# Fritzen_Zero_P_r00.net
KiCad netlist of a schematic drawn in EAGLE
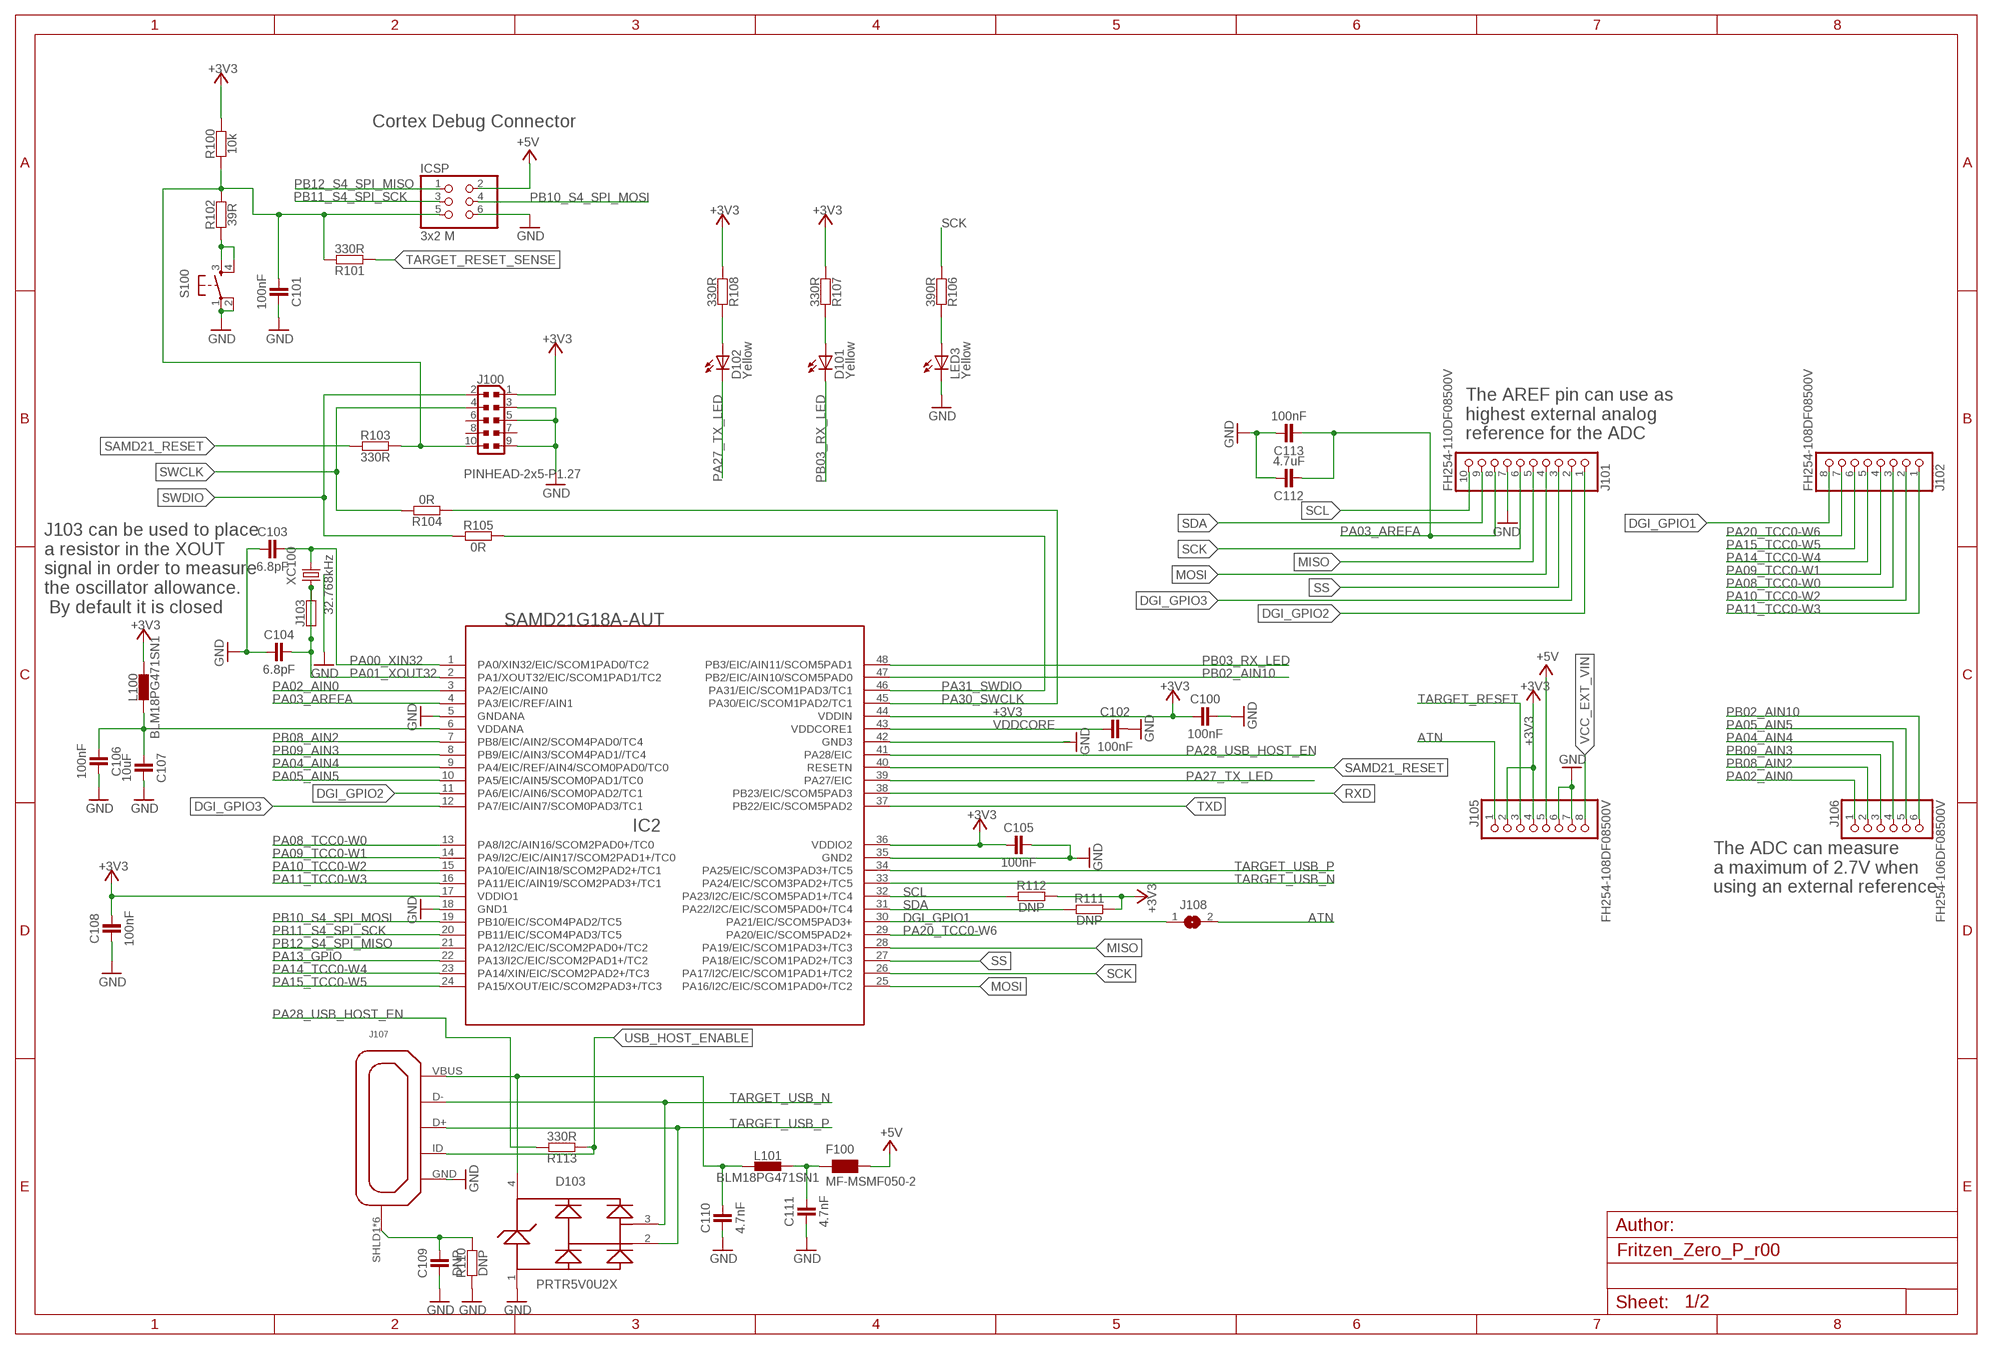
[diagram p0: schematic, sheet 1]
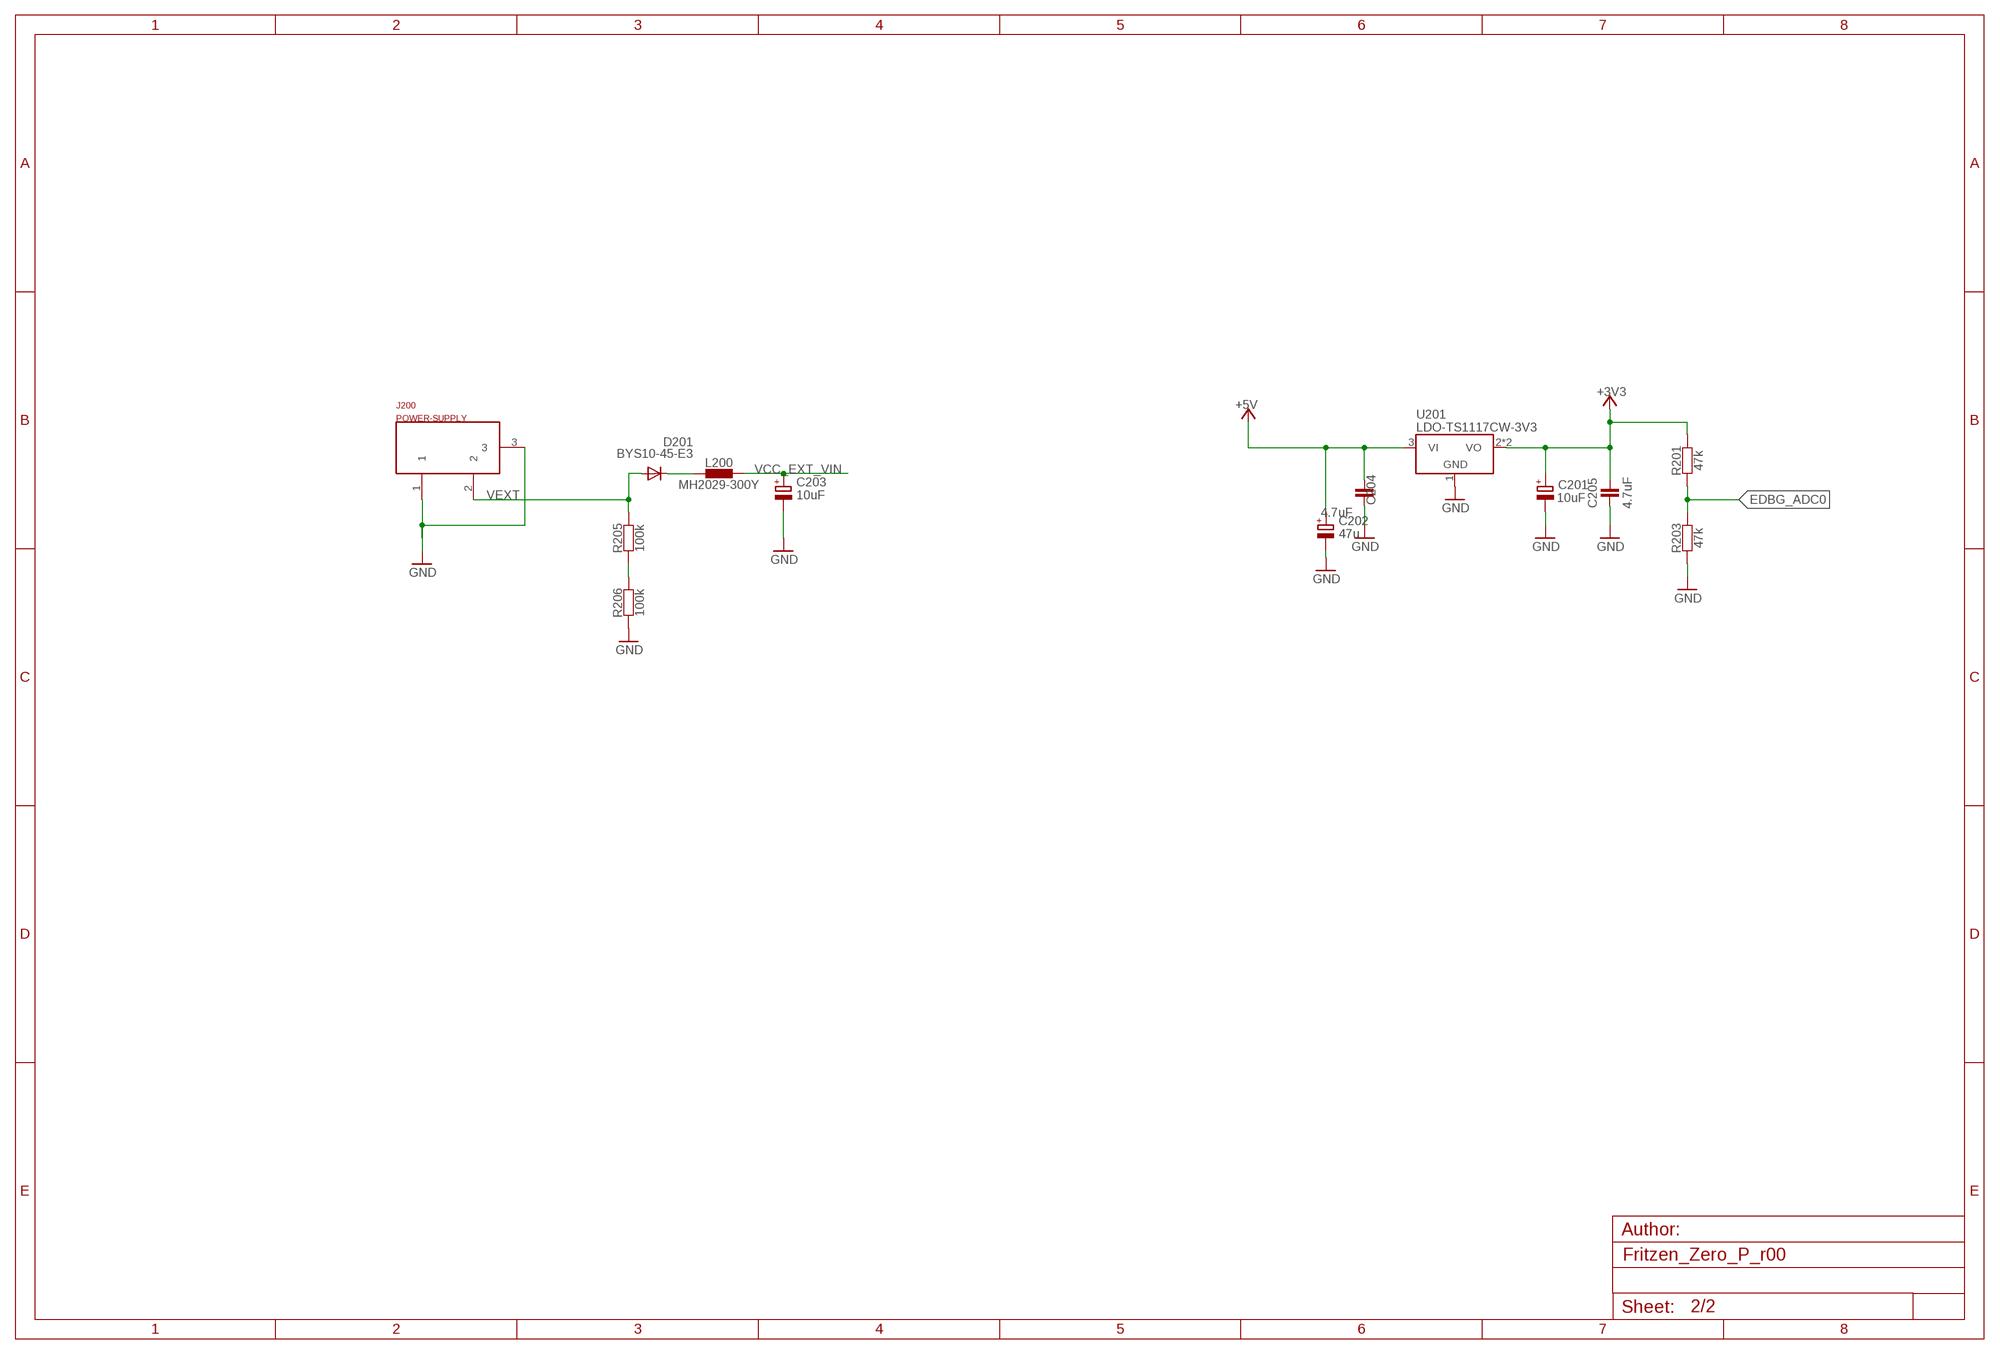
[diagram p1: schematic, sheet 2]

(export (version "E")
  (design (tool "Eeschema 10.0.6"))
  (components
    (comp (ref "C100")
      (value "100nF")
      (footprint "eagle-import:C0402")
      (libsource (lib "eagle-import") (part "CAPACITORS-0402"))
    )
    (comp (ref "C101")
      (value "100nF")
      (footprint "eagle-import:C0402")
      (libsource (lib "eagle-import") (part "CAPACITORS-0402"))
    )
    (comp (ref "C102")
      (value "100nF")
      (footprint "eagle-import:C0402")
      (libsource (lib "eagle-import") (part "CAPACITORS-0402"))
    )
    (comp (ref "C103")
      (value "6.8pF")
      (footprint "eagle-import:C0402")
      (libsource (lib "eagle-import") (part "CAPACITORS-0402"))
    )
    (comp (ref "C104")
      (value "6.8pF")
      (footprint "eagle-import:C0402")
      (libsource (lib "eagle-import") (part "CAPACITORS-0402"))
    )
    (comp (ref "C105")
      (value "100nF")
      (footprint "eagle-import:C0402")
      (libsource (lib "eagle-import") (part "CAPACITORS-0402"))
    )
    (comp (ref "C106")
      (value "100nF")
      (footprint "eagle-import:C0402")
      (libsource (lib "eagle-import") (part "CAPACITORS-0402"))
    )
    (comp (ref "C107")
      (value "10uF")
      (footprint "eagle-import:C0603")
      (libsource (lib "eagle-import") (part "CAPACITORS-0603"))
    )
    (comp (ref "C108")
      (value "100nF")
      (footprint "eagle-import:C0402")
      (libsource (lib "eagle-import") (part "CAPACITORS-0402"))
    )
    (comp (ref "C109")
      (value "DNP")
      (footprint "eagle-import:C0402")
      (libsource (lib "eagle-import") (part "CAPACITORS-0402"))
    )
    (comp (ref "C110")
      (value "4.7nF")
      (footprint "eagle-import:C0402")
      (libsource (lib "eagle-import") (part "CAPACITORS-0402"))
    )
    (comp (ref "C111")
      (value "4.7nF")
      (footprint "eagle-import:C0402")
      (libsource (lib "eagle-import") (part "CAPACITORS-0402"))
    )
    (comp (ref "C112")
      (value "4.7uF")
      (footprint "eagle-import:C0603")
      (libsource (lib "eagle-import") (part "CAPACITORS-0603"))
    )
    (comp (ref "C113")
      (value "100nF")
      (footprint "eagle-import:C0402")
      (libsource (lib "eagle-import") (part "CAPACITORS-0402"))
    )
    (comp (ref "D101")
      (value "Yellow")
      (footprint "eagle-import:CHIPLED_0805")
      (fields (field (name "PART_NUMBER") "KPT-2012YC"))
      (libsource (lib "eagle-import") (part "0044_KPT-2012YC"))
    )
    (comp (ref "D102")
      (value "Yellow")
      (footprint "eagle-import:CHIPLED_0805")
      (fields (field (name "PART_NUMBER") "KPT-2012YC"))
      (libsource (lib "eagle-import") (part "0044_KPT-2012YC"))
    )
    (comp (ref "D103")
      (value "PRTR5V0U2XB")
      (footprint "eagle-import:SOT143B")
      (libsource (lib "eagle-import") (part "PRTR5V0U2XB"))
    )
    (comp (ref "F100")
      (value "MF-MSMF050-2")
      (footprint "eagle-import:WUERTH-ELEKTRONIK_1812")
      (libsource (lib "eagle-import") (part "WUERTH-ELEKTRONIK_WE-CBF_1812"))
    )
    (comp (ref "IC2")
      (value "SAMD21G18A-AUT")
      (footprint "eagle-import:TQFP48")
      (libsource (lib "eagle-import") (part "SAMD21G18A"))
    )
    (comp (ref "ICSP")
      (value "3x2 M")
      (footprint "eagle-import:2X03")
      (libsource (lib "eagle-import") (part "ICSP"))
    )
    (comp (ref "J100")
      (value "PINHEAD-2x5-P1.27")
      (footprint "eagle-import:PINHEAD_2X05_127")
      (libsource (lib "eagle-import") (part "0171_PH127-205DF055G00AROUND-PADS"))
    )
    (comp (ref "J101")
      (value "FH254-110DF08500V")
      (footprint "eagle-import:1X10")
      (fields (field (name "PART_NUMBER") "20TW-537"))
      (libsource (lib "eagle-import") (part "1684_20TW-537"))
    )
    (comp (ref "J102")
      (value "FH254-108DF08500V")
      (footprint "eagle-import:1X08")
      (fields (field (name "PART_NUMBER") "20TW-536"))
      (libsource (lib "eagle-import") (part "1683_20TW-536"))
    )
    (comp (ref "J103")
      (value "RESISTORS-0402")
      (footprint "eagle-import:C0402")
      (libsource (lib "eagle-import") (part "RESISTORS-0402"))
    )
    (comp (ref "J105")
      (value "FH254-108DF08500V")
      (footprint "eagle-import:1X08")
      (fields (field (name "PART_NUMBER") "20TW-536"))
      (libsource (lib "eagle-import") (part "1683_20TW-536"))
    )
    (comp (ref "J106")
      (value "FH254-106DF08500V")
      (footprint "eagle-import:1X06")
      (fields (field (name "PART_NUMBER") "20TW-535"))
      (libsource (lib "eagle-import") (part "1682_20TW-535_STD"))
    )
    (comp (ref "J107")
      (value "ZX62-AB-5PA")
      (footprint "eagle-import:USB-MICRO-10103594")
      (libsource (lib "eagle-import") (part "ZX62-AB-5PA"))
    )
    (comp (ref "J108")
      (value "SJ")
      (footprint "eagle-import:SJ")
      (libsource (lib "eagle-import") (part "SJ"))
    )
    (comp (ref "L100")
      (value "BLM18PG471SN1")
      (footprint "eagle-import:C0603")
      (libsource (lib "eagle-import") (part "INDUCTOR-0603"))
    )
    (comp (ref "L101")
      (value "BLM18PG471SN1")
      (footprint "eagle-import:C0603")
      (libsource (lib "eagle-import") (part "INDUCTOR-0603"))
    )
    (comp (ref "LED3")
      (value "Yellow")
      (footprint "eagle-import:CHIPLED_0805")
      (fields (field (name "PART_NUMBER") "KPT-2012YC"))
      (libsource (lib "eagle-import") (part "0044_KPT-2012YC"))
    )
    (comp (ref "R100")
      (value "10k")
      (footprint "eagle-import:C0402")
      (libsource (lib "eagle-import") (part "RESISTORS-0402"))
    )
    (comp (ref "R101")
      (value "330R")
      (footprint "eagle-import:C0402")
      (libsource (lib "eagle-import") (part "RESISTORS-0402"))
    )
    (comp (ref "R102")
      (value "39R")
      (footprint "eagle-import:C0402")
      (libsource (lib "eagle-import") (part "RESISTORS-0402"))
    )
    (comp (ref "R103")
      (value "330R")
      (footprint "eagle-import:C0402")
      (libsource (lib "eagle-import") (part "RESISTORS-0402"))
    )
    (comp (ref "R104")
      (value "0R")
      (footprint "eagle-import:C0402")
      (libsource (lib "eagle-import") (part "RESISTORS-0402"))
    )
    (comp (ref "R105")
      (value "0R")
      (footprint "eagle-import:C0402")
      (libsource (lib "eagle-import") (part "RESISTORS-0402"))
    )
    (comp (ref "R106")
      (value "390R")
      (footprint "eagle-import:C0402")
      (libsource (lib "eagle-import") (part "RESISTORS-0402"))
    )
    (comp (ref "R107")
      (value "330R")
      (footprint "eagle-import:C0402")
      (libsource (lib "eagle-import") (part "RESISTORS-0402"))
    )
    (comp (ref "R108")
      (value "330R")
      (footprint "eagle-import:C0402")
      (libsource (lib "eagle-import") (part "RESISTORS-0402"))
    )
    (comp (ref "R110")
      (value "DNP")
      (footprint "eagle-import:C0402")
      (libsource (lib "eagle-import") (part "RESISTORS-0402"))
    )
    (comp (ref "R111")
      (value "DNP")
      (footprint "eagle-import:C0402")
      (libsource (lib "eagle-import") (part "RESISTORS-0402"))
    )
    (comp (ref "R112")
      (value "DNP")
      (footprint "eagle-import:C0402")
      (libsource (lib "eagle-import") (part "RESISTORS-0402"))
    )
    (comp (ref "R113")
      (value "330R")
      (footprint "eagle-import:C0402")
      (libsource (lib "eagle-import") (part "RESISTORS-0402"))
    )
    (comp (ref "S100")
      (value "PUSHBUTTON3")
      (footprint "eagle-import:TS42_4PINS")
      (libsource (lib "eagle-import") (part "PUSHBUTTON3"))
    )
    (comp (ref "XC100")
      (value "32.768kHz")
      (footprint "eagle-import:CRYSTAL_TC26SMD")
      (libsource (lib "eagle-import") (part "CRYSTALSMD"))
    )
    (comp (ref "C201")
      (value "10uF")
      (footprint "eagle-import:PANASONIC_D")
      (fields (field (name "PART_NUMBER") "47uF"))
      (libsource (lib "eagle-import") (part "0113_47UF"))
    )
    (comp (ref "C202")
      (value "47u")
      (footprint "eagle-import:PANASONIC_D")
      (fields (field (name "PART_NUMBER") "47uF"))
      (libsource (lib "eagle-import") (part "0113_47UF"))
    )
    (comp (ref "C203")
      (value "10uF")
      (footprint "eagle-import:PANASONIC_D")
      (fields (field (name "PART_NUMBER") "47uF"))
      (libsource (lib "eagle-import") (part "0113_47UF"))
    )
    (comp (ref "C204")
      (value "4.7uF")
      (footprint "eagle-import:C0603")
      (libsource (lib "eagle-import") (part "CAPACITORS-0603"))
    )
    (comp (ref "C205")
      (value "4.7uF")
      (footprint "eagle-import:C0603")
      (libsource (lib "eagle-import") (part "CAPACITORS-0603"))
    )
    (comp (ref "D201")
      (value "BYS10-45-E3")
      (footprint "eagle-import:MINIMELF")
      (fields (field (name "PART_NUMBER") "CD1206-S01575"))
      (libsource (lib "eagle-import") (part "0012_CD1206-S01575"))
    )
    (comp (ref "J200")
      (value "POWER-SUPPLY")
      (footprint "eagle-import:POWERSUPPLY_DC-21MM")
      (fields (field (name "PART_NUMBER") "19746"))
      (libsource (lib "eagle-import") (part "0018_19746-POWER-SUPPLY"))
    )
    (comp (ref "L200")
      (value "MH2029-300Y")
      (footprint "eagle-import:C0805")
      (libsource (lib "eagle-import") (part "INDUCTOR-0805"))
    )
    (comp (ref "R201")
      (value "47k")
      (footprint "eagle-import:C0402")
      (libsource (lib "eagle-import") (part "RESISTORS-0402"))
    )
    (comp (ref "R203")
      (value "47k")
      (footprint "eagle-import:C0402")
      (libsource (lib "eagle-import") (part "RESISTORS-0402"))
    )
    (comp (ref "R205")
      (value "100k")
      (footprint "eagle-import:C0402")
      (libsource (lib "eagle-import") (part "RESISTORS-0402"))
    )
    (comp (ref "R206")
      (value "100k")
      (footprint "eagle-import:C0402")
      (libsource (lib "eagle-import") (part "RESISTORS-0402"))
    )
    (comp (ref "U201")
      (value "LDO-TS1117CW-3V3")
      (footprint "eagle-import:SOT223")
      (libsource (lib "eagle-import") (part "LDO-TS1117CW-3V3"))
    )
  )
  (nets
    (net (code "1") (name "+3V3") (class "Default")
      (node (ref "C100") (pin "1") (pinfunction "1_1") (pintype "passive"))
      (node (ref "C105") (pin "1") (pinfunction "1_1") (pintype "passive"))
      (node (ref "C108") (pin "2") (pinfunction "2_2") (pintype "passive"))
      (node (ref "C201") (pin "+") (pinfunction "+_+") (pintype "passive"))
      (node (ref "C205") (pin "2") (pinfunction "2_2") (pintype "passive"))
      (node (ref "IC2") (pin "17") (pinfunction "VDDIO1_17") (pintype "power_in"))
      (node (ref "IC2") (pin "36") (pinfunction "VDDIO2_36") (pintype "power_in"))
      (node (ref "IC2") (pin "44") (pinfunction "VDDIN_44") (pintype "power_in"))
      (node (ref "J100") (pin "1") (pinfunction "1_1") (pintype "passive"))
      (node (ref "J105") (pin "2") (pinfunction "2_2") (pintype "passive"))
      (node (ref "J105") (pin "4") (pinfunction "4_4") (pintype "passive"))
      (node (ref "L100") (pin "2") (pinfunction "2_2") (pintype "passive"))
      (node (ref "R100") (pin "2") (pinfunction "2_2") (pintype "passive"))
      (node (ref "R107") (pin "1") (pinfunction "1_1") (pintype "passive"))
      (node (ref "R108") (pin "1") (pinfunction "1_1") (pintype "passive"))
      (node (ref "R111") (pin "2") (pinfunction "2_2") (pintype "passive"))
      (node (ref "R112") (pin "2") (pinfunction "2_2") (pintype "passive"))
      (node (ref "R201") (pin "2") (pinfunction "2_2") (pintype "passive"))
      (node (ref "U201") (pin "2") (pinfunction "VO_2") (pintype "passive"))
      (node (ref "U201") (pin "4") (pinfunction "VO_4") (pintype "passive"))
    )
    (net (code "2") (name "+5V") (class "Default")
      (node (ref "C202") (pin "+") (pinfunction "+_+") (pintype "passive"))
      (node (ref "C204") (pin "1") (pinfunction "1_1") (pintype "passive"))
      (node (ref "F100") (pin "2") (pinfunction "2_2") (pintype "passive"))
      (node (ref "ICSP") (pin "2") (pinfunction "2_2") (pintype "passive"))
      (node (ref "J105") (pin "5") (pinfunction "5_5") (pintype "passive"))
      (node (ref "U201") (pin "3") (pinfunction "VI_3") (pintype "input"))
    )
    (net (code "3") (name "ATN") (class "Default")
      (node (ref "J105") (pin "1") (pinfunction "1_1") (pintype "passive"))
      (node (ref "J108") (pin "2") (pinfunction "2_2") (pintype "passive"))
    )
    (net (code "4") (name "DGI_GPIO1") (class "Default")
      (node (ref "IC2") (pin "30") (pinfunction "PA21/EIC/SCOM5PAD3+_30") (pintype "bidirectional"))
      (node (ref "J102") (pin "8") (pinfunction "8_8") (pintype "passive"))
      (node (ref "J108") (pin "1") (pinfunction "1_1") (pintype "passive"))
    )
    (net (code "5") (name "DGI_GPIO2") (class "Default")
      (node (ref "IC2") (pin "11") (pinfunction "PA6/EIC/AIN6/SCOM0PAD2/TC1_11") (pintype "bidirectional"))
      (node (ref "J101") (pin "1") (pinfunction "1_1") (pintype "passive"))
    )
    (net (code "6") (name "DGI_GPIO3") (class "Default")
      (node (ref "IC2") (pin "12") (pinfunction "PA7/EIC/AIN7/SCOM0PAD3/TC1_12") (pintype "bidirectional"))
      (node (ref "J101") (pin "2") (pinfunction "2_2") (pintype "passive"))
    )
    (net (code "7") (name "EDBG_ADC0") (class "Default")
      (node (ref "R201") (pin "1") (pinfunction "1_1") (pintype "passive"))
      (node (ref "R203") (pin "2") (pinfunction "2_2") (pintype "passive"))
    )
    (net (code "8") (name "GND") (class "Default")
      (node (ref "C100") (pin "2") (pinfunction "2_2") (pintype "passive"))
      (node (ref "C101") (pin "2") (pinfunction "2_2") (pintype "passive"))
      (node (ref "C102") (pin "2") (pinfunction "2_2") (pintype "passive"))
      (node (ref "C103") (pin "1") (pinfunction "1_1") (pintype "passive"))
      (node (ref "C104") (pin "1") (pinfunction "1_1") (pintype "passive"))
      (node (ref "C105") (pin "2") (pinfunction "2_2") (pintype "passive"))
      (node (ref "C106") (pin "2") (pinfunction "2_2") (pintype "passive"))
      (node (ref "C107") (pin "2") (pinfunction "2_2") (pintype "passive"))
      (node (ref "C108") (pin "1") (pinfunction "1_1") (pintype "passive"))
      (node (ref "C109") (pin "1") (pinfunction "1_1") (pintype "passive"))
      (node (ref "C110") (pin "1") (pinfunction "1_1") (pintype "passive"))
      (node (ref "C111") (pin "1") (pinfunction "1_1") (pintype "passive"))
      (node (ref "C112") (pin "2") (pinfunction "2_2") (pintype "passive"))
      (node (ref "C113") (pin "2") (pinfunction "2_2") (pintype "passive"))
      (node (ref "C201") (pin "-") (pinfunction "-_-") (pintype "passive"))
      (node (ref "C202") (pin "-") (pinfunction "-_-") (pintype "passive"))
      (node (ref "C203") (pin "-") (pinfunction "-_-") (pintype "passive"))
      (node (ref "C204") (pin "2") (pinfunction "2_2") (pintype "passive"))
      (node (ref "C205") (pin "1") (pinfunction "1_1") (pintype "passive"))
      (node (ref "D103") (pin "1") (pinfunction "1_1") (pintype "bidirectional"))
      (node (ref "IC2") (pin "18") (pinfunction "GND1_18") (pintype "power_in"))
      (node (ref "IC2") (pin "35") (pinfunction "GND2_35") (pintype "power_in"))
      (node (ref "IC2") (pin "42") (pinfunction "GND3_42") (pintype "power_in"))
      (node (ref "IC2") (pin "5") (pinfunction "GNDANA_5") (pintype "power_in"))
      (node (ref "ICSP") (pin "6") (pinfunction "6_6") (pintype "passive"))
      (node (ref "J100") (pin "3") (pinfunction "3_3") (pintype "passive"))
      (node (ref "J100") (pin "5") (pinfunction "5_5") (pintype "passive"))
      (node (ref "J100") (pin "9") (pinfunction "9_9") (pintype "passive"))
      (node (ref "J101") (pin "7") (pinfunction "7_7") (pintype "passive"))
      (node (ref "J105") (pin "6") (pinfunction "6_6") (pintype "passive"))
      (node (ref "J105") (pin "7") (pinfunction "7_7") (pintype "passive"))
      (node (ref "J107") (pin "GND") (pinfunction "GND_GND") (pintype "bidirectional"))
      (node (ref "J200") (pin "1") (pinfunction "1_1") (pintype "power_in"))
      (node (ref "J200") (pin "3") (pinfunction "3_3") (pintype "power_in"))
      (node (ref "LED3") (pin "C") (pinfunction "C_C") (pintype "passive"))
      (node (ref "R110") (pin "1") (pinfunction "1_1") (pintype "passive"))
      (node (ref "R203") (pin "1") (pinfunction "1_1") (pintype "passive"))
      (node (ref "R206") (pin "1") (pinfunction "1_1") (pintype "passive"))
      (node (ref "S100") (pin "1") (pinfunction "1_1") (pintype "passive"))
      (node (ref "S100") (pin "2") (pinfunction "2_2") (pintype "passive"))
      (node (ref "U201") (pin "1") (pinfunction "GND_1") (pintype "passive"))
      (node (ref "XC100") (pin "P$1") (pinfunction "GND_P$1") (pintype "bidirectional"))
    )
    (net (code "9") (name "MISO") (class "Default")
      (node (ref "IC2") (pin "28") (pinfunction "PA19/EIC/SCOM1PAD3+/TC3_28") (pintype "bidirectional"))
      (node (ref "J101") (pin "5") (pinfunction "5_5") (pintype "passive"))
    )
    (net (code "10") (name "MOSI") (class "Default")
      (node (ref "IC2") (pin "25") (pinfunction "PA16/I2C/EIC/SCOM1PAD0+/TC2_25") (pintype "bidirectional"))
      (node (ref "J101") (pin "4") (pinfunction "4_4") (pintype "passive"))
    )
    (net (code "11") (name "Net-(C109-Pad2)") (class "Default")
      (node (ref "C109") (pin "2") (pinfunction "2_2") (pintype "passive"))
      (node (ref "J107") (pin "SHLD1") (pinfunction "SH_SHLD1") (pintype "bidirectional"))
      (node (ref "J107") (pin "SHLD2") (pinfunction "SH_SHLD2") (pintype "bidirectional"))
      (node (ref "J107") (pin "SHLD3") (pinfunction "SH_SHLD3") (pintype "bidirectional"))
      (node (ref "J107") (pin "SHLD4") (pinfunction "SH_SHLD4") (pintype "bidirectional"))
      (node (ref "J107") (pin "SHLD5") (pinfunction "SH_SHLD5") (pintype "bidirectional"))
      (node (ref "J107") (pin "SHLD6") (pinfunction "SH_SHLD6") (pintype "bidirectional"))
      (node (ref "R110") (pin "2") (pinfunction "2_2") (pintype "passive"))
    )
    (net (code "12") (name "Net-(C111-Pad2)") (class "Default")
      (node (ref "C111") (pin "2") (pinfunction "2_2") (pintype "passive"))
      (node (ref "F100") (pin "1") (pinfunction "1_1") (pintype "passive"))
      (node (ref "L101") (pin "2") (pinfunction "2_2") (pintype "passive"))
    )
    (net (code "13") (name "Net-(D101-PadA)") (class "Default")
      (node (ref "D101") (pin "A") (pinfunction "A_A") (pintype "passive"))
      (node (ref "R107") (pin "2") (pinfunction "2_2") (pintype "passive"))
    )
    (net (code "14") (name "Net-(D102-PadA)") (class "Default")
      (node (ref "D102") (pin "A") (pinfunction "A_A") (pintype "passive"))
      (node (ref "R108") (pin "2") (pinfunction "2_2") (pintype "passive"))
    )
    (net (code "15") (name "Net-(D201-PadC)") (class "Default")
      (node (ref "D201") (pin "C") (pinfunction "C_C") (pintype "passive"))
      (node (ref "L200") (pin "1") (pinfunction "1_1") (pintype "passive"))
    )
    (net (code "16") (name "Net-(IC2-VDDANA)") (class "Default")
      (node (ref "C106") (pin "1") (pinfunction "1_1") (pintype "passive"))
      (node (ref "C107") (pin "1") (pinfunction "1_1") (pintype "passive"))
      (node (ref "IC2") (pin "6") (pinfunction "VDDANA_6") (pintype "power_in"))
      (node (ref "L100") (pin "1") (pinfunction "1_1") (pintype "passive"))
    )
    (net (code "17") (name "Net-(J107-VUSB)") (class "Default")
      (node (ref "C110") (pin "2") (pinfunction "2_2") (pintype "passive"))
      (node (ref "D103") (pin "4") (pinfunction "4_4") (pintype "bidirectional"))
      (node (ref "J107") (pin "VBUS") (pinfunction "VUSB_VBUS") (pintype "bidirectional"))
      (node (ref "L101") (pin "1") (pinfunction "1_1") (pintype "passive"))
    )
    (net (code "18") (name "Net-(LED3-PadA)") (class "Default")
      (node (ref "LED3") (pin "A") (pinfunction "A_A") (pintype "passive"))
      (node (ref "R106") (pin "2") (pinfunction "2_2") (pintype "passive"))
    )
    (net (code "19") (name "Net-(R102-Pad1)") (class "Default")
      (node (ref "R102") (pin "1") (pinfunction "1_1") (pintype "passive"))
      (node (ref "S100") (pin "3") (pinfunction "3_3") (pintype "passive"))
      (node (ref "S100") (pin "4") (pinfunction "4_4") (pintype "passive"))
    )
    (net (code "20") (name "Net-(R205-Pad1)") (class "Default")
      (node (ref "R205") (pin "1") (pinfunction "1_1") (pintype "passive"))
      (node (ref "R206") (pin "2") (pinfunction "2_2") (pintype "passive"))
    )
    (net (code "21") (name "PA00_XIN32") (class "Default")
      (node (ref "C103") (pin "2") (pinfunction "2_2") (pintype "passive"))
      (node (ref "IC2") (pin "1") (pinfunction "PA0/XIN32/EIC/SCOM1PAD0/TC2_1") (pintype "bidirectional"))
      (node (ref "XC100") (pin "2") (pinfunction "2_2") (pintype "passive"))
    )
    (net (code "22") (name "PA01_XOUT32") (class "Default")
      (node (ref "C104") (pin "2") (pinfunction "2_2") (pintype "passive"))
      (node (ref "IC2") (pin "2") (pinfunction "PA1/XOUT32/EIC/SCOM1PAD1/TC2_2") (pintype "bidirectional"))
      (node (ref "J103") (pin "1") (pinfunction "1_1") (pintype "passive"))
      (node (ref "J103") (pin "2") (pinfunction "2_2") (pintype "passive"))
      (node (ref "XC100") (pin "1") (pinfunction "1_1") (pintype "passive"))
    )
    (net (code "23") (name "PA02_AIN0") (class "Default")
      (node (ref "IC2") (pin "3") (pinfunction "PA2/EIC/AIN0_3") (pintype "bidirectional"))
      (node (ref "J106") (pin "1") (pinfunction "1_1") (pintype "passive"))
    )
    (net (code "24") (name "PA03_AREFA") (class "Default")
      (node (ref "C112") (pin "1") (pinfunction "1_1") (pintype "passive"))
      (node (ref "C113") (pin "1") (pinfunction "1_1") (pintype "passive"))
      (node (ref "IC2") (pin "4") (pinfunction "PA3/EIC/REF/AIN1_4") (pintype "bidirectional"))
      (node (ref "J101") (pin "8") (pinfunction "8_8") (pintype "passive"))
    )
    (net (code "25") (name "PA04_AIN4") (class "Default")
      (node (ref "IC2") (pin "9") (pinfunction "PA4/EIC/REF/AIN4/SCOM0PAD0/TC0_9") (pintype "bidirectional"))
      (node (ref "J106") (pin "4") (pinfunction "4_4") (pintype "passive"))
    )
    (net (code "26") (name "PA05_AIN5") (class "Default")
      (node (ref "IC2") (pin "10") (pinfunction "PA5/EIC/AIN5/SCOM0PAD1/TC0_10") (pintype "bidirectional"))
      (node (ref "J106") (pin "5") (pinfunction "5_5") (pintype "passive"))
    )
    (net (code "27") (name "PA08_TCC0-W0") (class "Default")
      (node (ref "IC2") (pin "13") (pinfunction "PA8/I2C/AIN16/SCOM2PAD0+/TC0_13") (pintype "bidirectional"))
      (node (ref "J102") (pin "3") (pinfunction "3_3") (pintype "passive"))
    )
    (net (code "28") (name "PA09_TCC0-W1") (class "Default")
      (node (ref "IC2") (pin "14") (pinfunction "PA9/I2C/EIC/AIN17/SCOM2PAD1+/TC0_14") (pintype "bidirectional"))
      (node (ref "J102") (pin "4") (pinfunction "4_4") (pintype "passive"))
    )
    (net (code "29") (name "PA10_TCC0-W2") (class "Default")
      (node (ref "IC2") (pin "15") (pinfunction "PA10/EIC/AIN18/SCOM2PAD2+/TC1_15") (pintype "bidirectional"))
      (node (ref "J102") (pin "2") (pinfunction "2_2") (pintype "passive"))
    )
    (net (code "30") (name "PA11_TCC0-W3") (class "Default")
      (node (ref "IC2") (pin "16") (pinfunction "PA11/EIC/AIN19/SCOM2PAD3+/TC1_16") (pintype "bidirectional"))
      (node (ref "J102") (pin "1") (pinfunction "1_1") (pintype "passive"))
    )
    (net (code "31") (name "PA13_GPIO") (class "Default")
      (node (ref "IC2") (pin "22") (pinfunction "PA13/I2C/EIC/SCOM2PAD1+/TC2_22") (pintype "bidirectional"))
    )
    (net (code "32") (name "PA14_TCC0-W4") (class "Default")
      (node (ref "IC2") (pin "23") (pinfunction "PA14/XIN/EIC/SCOM2PAD2+/TC3_23") (pintype "bidirectional"))
      (node (ref "J102") (pin "5") (pinfunction "5_5") (pintype "passive"))
    )
    (net (code "33") (name "PA15_TCC0-W5") (class "Default")
      (node (ref "IC2") (pin "24") (pinfunction "PA15/XOUT/EIC/SCOM2PAD3+/TC3_24") (pintype "bidirectional"))
      (node (ref "J102") (pin "6") (pinfunction "6_6") (pintype "passive"))
    )
    (net (code "34") (name "PA20_TCC0-W6") (class "Default")
      (node (ref "IC2") (pin "29") (pinfunction "PA20/EIC/SCOM5PAD2+_29") (pintype "bidirectional"))
      (node (ref "J102") (pin "7") (pinfunction "7_7") (pintype "passive"))
    )
    (net (code "35") (name "PA27_TX_LED") (class "Default")
      (node (ref "D102") (pin "C") (pinfunction "C_C") (pintype "passive"))
      (node (ref "IC2") (pin "39") (pinfunction "PA27/EIC_39") (pintype "bidirectional"))
    )
    (net (code "36") (name "PA28_USB_HOST_EN") (class "Default")
      (node (ref "IC2") (pin "41") (pinfunction "PA28/EIC_41") (pintype "bidirectional"))
      (node (ref "R113") (pin "2") (pinfunction "2_2") (pintype "passive"))
    )
    (net (code "37") (name "PA30_SWCLK") (class "Default")
      (node (ref "IC2") (pin "45") (pinfunction "PA30/EIC/SCOM1PAD2/TC1_45") (pintype "bidirectional"))
      (node (ref "R104") (pin "1") (pinfunction "1_1") (pintype "passive"))
    )
    (net (code "38") (name "PA31_SWDIO") (class "Default")
      (node (ref "IC2") (pin "46") (pinfunction "PA31/EIC/SCOM1PAD3/TC1_46") (pintype "bidirectional"))
      (node (ref "R105") (pin "2") (pinfunction "2_2") (pintype "passive"))
    )
    (net (code "39") (name "PB02_AIN10") (class "Default")
      (node (ref "IC2") (pin "47") (pinfunction "PB2/EIC/AIN10/SCOM5PAD0_47") (pintype "bidirectional"))
      (node (ref "J106") (pin "6") (pinfunction "6_6") (pintype "passive"))
    )
    (net (code "40") (name "PB03_RX_LED") (class "Default")
      (node (ref "D101") (pin "C") (pinfunction "C_C") (pintype "passive"))
      (node (ref "IC2") (pin "48") (pinfunction "PB3/EIC/AIN11/SCOM5PAD1_48") (pintype "bidirectional"))
    )
    (net (code "41") (name "PB08_AIN2") (class "Default")
      (node (ref "IC2") (pin "7") (pinfunction "PB8/EIC/AIN2/SCOM4PAD0/TC4_7") (pintype "bidirectional"))
      (node (ref "J106") (pin "2") (pinfunction "2_2") (pintype "passive"))
    )
    (net (code "42") (name "PB09_AIN3") (class "Default")
      (node (ref "IC2") (pin "8") (pinfunction "PB9/EIC/AIN3/SCOM4PAD1//TC4_8") (pintype "bidirectional"))
      (node (ref "J106") (pin "3") (pinfunction "3_3") (pintype "passive"))
    )
    (net (code "43") (name "PB10_S4_SPI_MOSI") (class "Default")
      (node (ref "IC2") (pin "19") (pinfunction "PB10/EIC/SCOM4PAD2/TC5_19") (pintype "bidirectional"))
      (node (ref "ICSP") (pin "4") (pinfunction "4_4") (pintype "passive"))
    )
    (net (code "44") (name "PB11_S4_SPI_SCK") (class "Default")
      (node (ref "IC2") (pin "20") (pinfunction "PB11/EIC/SCOM4PAD3/TC5_20") (pintype "bidirectional"))
      (node (ref "ICSP") (pin "3") (pinfunction "3_3") (pintype "passive"))
    )
    (net (code "45") (name "PB12_S4_SPI_MISO") (class "Default")
      (node (ref "IC2") (pin "21") (pinfunction "PA12/I2C/EIC/SCOM2PAD0+/TC2_21") (pintype "bidirectional"))
      (node (ref "ICSP") (pin "1") (pinfunction "1_1") (pintype "passive"))
    )
    (net (code "46") (name "RXD") (class "Default")
      (node (ref "IC2") (pin "38") (pinfunction "PB23/EIC/SCOM5PAD3_38") (pintype "bidirectional"))
    )
    (net (code "47") (name "SAMD21_RESET") (class "Default")
      (node (ref "IC2") (pin "40") (pinfunction "RESETN_40") (pintype "bidirectional"))
      (node (ref "R103") (pin "1") (pinfunction "1_1") (pintype "passive"))
    )
    (net (code "48") (name "SCK") (class "Default")
      (node (ref "IC2") (pin "26") (pinfunction "PA17/I2C/EIC/SCOM1PAD1+/TC2_26") (pintype "bidirectional"))
      (node (ref "J101") (pin "6") (pinfunction "6_6") (pintype "passive"))
      (node (ref "R106") (pin "1") (pinfunction "1_1") (pintype "passive"))
    )
    (net (code "49") (name "SCL") (class "Default")
      (node (ref "IC2") (pin "32") (pinfunction "PA23/I2C/EIC/SCOM5PAD1+/TC4_32") (pintype "bidirectional"))
      (node (ref "J101") (pin "10") (pinfunction "10_10") (pintype "passive"))
      (node (ref "R112") (pin "1") (pinfunction "1_1") (pintype "passive"))
    )
    (net (code "50") (name "SDA") (class "Default")
      (node (ref "IC2") (pin "31") (pinfunction "PA22/I2C/EIC/SCOM5PAD0+/TC4_31") (pintype "bidirectional"))
      (node (ref "J101") (pin "9") (pinfunction "9_9") (pintype "passive"))
      (node (ref "R111") (pin "1") (pinfunction "1_1") (pintype "passive"))
    )
    (net (code "51") (name "SS") (class "Default")
      (node (ref "IC2") (pin "27") (pinfunction "PA18/EIC/SCOM1PAD2+/TC3_27") (pintype "bidirectional"))
      (node (ref "J101") (pin "3") (pinfunction "3_3") (pintype "passive"))
    )
    (net (code "52") (name "SWCLK") (class "Default")
      (node (ref "J100") (pin "4") (pinfunction "4_4") (pintype "passive"))
      (node (ref "R104") (pin "2") (pinfunction "2_2") (pintype "passive"))
    )
    (net (code "53") (name "SWDIO") (class "Default")
      (node (ref "J100") (pin "2") (pinfunction "2_2") (pintype "passive"))
      (node (ref "R105") (pin "1") (pinfunction "1_1") (pintype "passive"))
    )
    (net (code "54") (name "TARGET_RESET") (class "Default")
      (node (ref "C101") (pin "1") (pinfunction "1_1") (pintype "passive"))
      (node (ref "ICSP") (pin "5") (pinfunction "5_5") (pintype "passive"))
      (node (ref "J100") (pin "10") (pinfunction "10_10") (pintype "passive"))
      (node (ref "J105") (pin "3") (pinfunction "3_3") (pintype "passive"))
      (node (ref "R100") (pin "1") (pinfunction "1_1") (pintype "passive"))
      (node (ref "R101") (pin "2") (pinfunction "2_2") (pintype "passive"))
      (node (ref "R102") (pin "2") (pinfunction "2_2") (pintype "passive"))
      (node (ref "R103") (pin "2") (pinfunction "2_2") (pintype "passive"))
    )
    (net (code "55") (name "TARGET_RESET_SENSE") (class "Default")
      (node (ref "R101") (pin "1") (pinfunction "1_1") (pintype "passive"))
    )
    (net (code "56") (name "TARGET_USB_N") (class "Default")
      (node (ref "D103") (pin "3") (pinfunction "3_3") (pintype "bidirectional"))
      (node (ref "IC2") (pin "33") (pinfunction "PA24/EIC/SCOM3PAD2+/TC5_33") (pintype "bidirectional"))
      (node (ref "J107") (pin "D-") (pinfunction "D-_D-") (pintype "bidirectional"))
    )
    (net (code "57") (name "TARGET_USB_P") (class "Default")
      (node (ref "D103") (pin "2") (pinfunction "2_2") (pintype "bidirectional"))
      (node (ref "IC2") (pin "34") (pinfunction "PA25/EIC/SCOM3PAD3+/TC5_34") (pintype "bidirectional"))
      (node (ref "J107") (pin "D+") (pinfunction "D+_D+") (pintype "bidirectional"))
    )
    (net (code "58") (name "TXD") (class "Default")
      (node (ref "IC2") (pin "37") (pinfunction "PB22/EIC/SCOM5PAD2_37") (pintype "bidirectional"))
    )
    (net (code "59") (name "USB_HOST_ENABLE") (class "Default")
      (node (ref "J107") (pin "ID") (pinfunction "ID_ID") (pintype "bidirectional"))
      (node (ref "R113") (pin "1") (pinfunction "1_1") (pintype "passive"))
    )
    (net (code "60") (name "VCC_EXT_VIN") (class "Default")
      (node (ref "C203") (pin "+") (pinfunction "+_+") (pintype "passive"))
      (node (ref "J105") (pin "8") (pinfunction "8_8") (pintype "passive"))
      (node (ref "L200") (pin "2") (pinfunction "2_2") (pintype "passive"))
    )
    (net (code "61") (name "VDDCORE") (class "Default")
      (node (ref "C102") (pin "1") (pinfunction "1_1") (pintype "passive"))
      (node (ref "IC2") (pin "43") (pinfunction "VDDCORE1_43") (pintype "input"))
    )
    (net (code "62") (name "VEXT") (class "Default")
      (node (ref "D201") (pin "A") (pinfunction "A_A") (pintype "passive"))
      (node (ref "J200") (pin "2") (pinfunction "2_2") (pintype "power_in"))
      (node (ref "R205") (pin "2") (pinfunction "2_2") (pintype "passive"))
    )
    (net (code "63") (name "unconnected-(J100-Pad6)") (class "Default")
      (node (ref "J100") (pin "6") (pinfunction "6_6") (pintype "passive"))
    )
    (net (code "64") (name "unconnected-(J100-Pad7)") (class "Default")
      (node (ref "J100") (pin "7") (pinfunction "7_7") (pintype "passive"))
    )
    (net (code "65") (name "unconnected-(J100-Pad8)") (class "Default")
      (node (ref "J100") (pin "8") (pinfunction "8_8") (pintype "passive"))
    )
  )
)
